# Power.net
KiCad netlist of a schematic drawn in Altium Designer
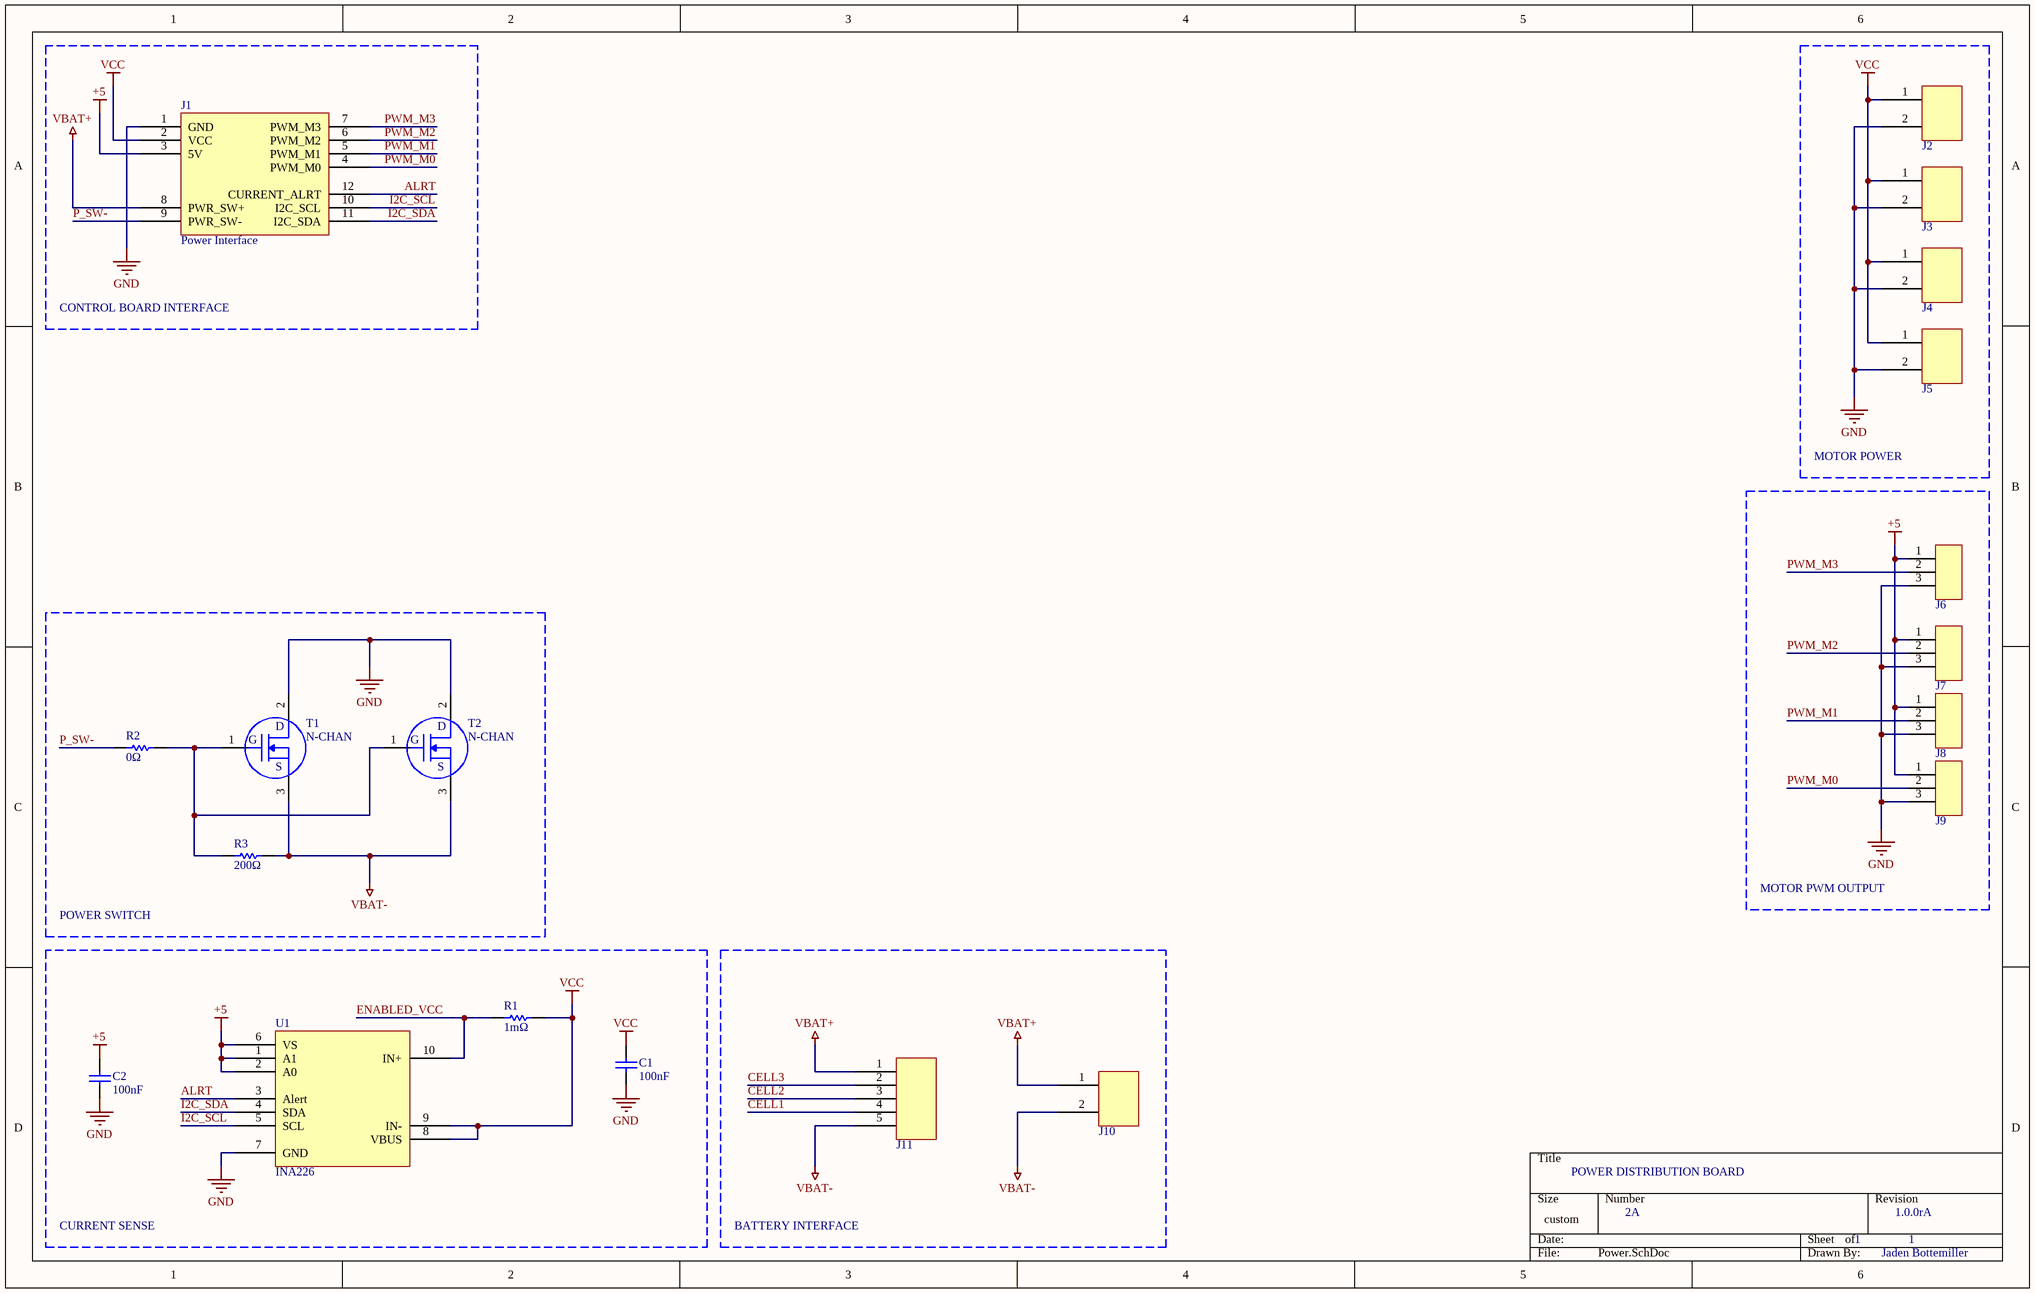
[diagram p0: Power.SchDoc]

(export (version "E")
  (design (tool "Eeschema 10.0.6"))
  (components
    (comp (ref "C1")
      (value "100nF")
      (description "Standard Capacitor")
      (fields (field (name "Comment") "CAP"))
      (libsource (lib "NikoboticsLib") (part "CAP"))
    )
    (comp (ref "C2")
      (value "100nF")
      (description "Standard Capacitor")
      (fields (field (name "Comment") "CAP"))
      (libsource (lib "NikoboticsLib") (part "CAP"))
    )
    (comp (ref "J1")
      (value "Power Interface")
      (description "Interface between power board and control board.")
      (libsource (lib "NikoboticsLib") (part "PDB_INTERFACE"))
    )
    (comp (ref "J2")
      (value "Power Connector")
      (description "Standard Power Connector")
      (libsource (lib "NikoboticsLib") (part "POWER_CONN"))
    )
    (comp (ref "J3")
      (value "Power Connector")
      (description "Standard Power Connector")
      (libsource (lib "NikoboticsLib") (part "POWER_CONN"))
    )
    (comp (ref "J4")
      (value "Power Connector")
      (description "Standard Power Connector")
      (libsource (lib "NikoboticsLib") (part "POWER_CONN"))
    )
    (comp (ref "J5")
      (value "Power Connector")
      (description "Standard Power Connector")
      (libsource (lib "NikoboticsLib") (part "POWER_CONN"))
    )
    (comp (ref "J6")
      (value "3-Pin Signal")
      (description "Standard 3-Pin Signal Connection")
      (libsource (lib "NikoboticsLib") (part "SIG_3PIN"))
    )
    (comp (ref "J7")
      (value "3-Pin Signal")
      (description "Standard 3-Pin Signal Connection")
      (libsource (lib "NikoboticsLib") (part "SIG_3PIN"))
    )
    (comp (ref "J8")
      (value "3-Pin Signal")
      (description "Standard 3-Pin Signal Connection")
      (libsource (lib "NikoboticsLib") (part "SIG_3PIN"))
    )
    (comp (ref "J9")
      (value "3-Pin Signal")
      (description "Standard 3-Pin Signal Connection")
      (libsource (lib "NikoboticsLib") (part "SIG_3PIN"))
    )
    (comp (ref "J10")
      (value "Power Connector")
      (description "Standard Power Connector")
      (libsource (lib "NikoboticsLib") (part "POWER_CONN"))
    )
    (comp (ref "J11")
      (value "5 Pin Connector")
      (description "Standard 5 Pin Connector")
      (libsource (lib "NikoboticsLib") (part "CONN_5PIN"))
    )
    (comp (ref "R1")
      (value "1mΩ")
      (description "Standard Resistor")
      (fields (field (name "Comment") "RES"))
      (libsource (lib "NikoboticsLib") (part "RES"))
    )
    (comp (ref "R2")
      (value "0Ω")
      (description "Standard Resistor")
      (fields (field (name "Comment") "RES"))
      (libsource (lib "NikoboticsLib") (part "RES"))
    )
    (comp (ref "R3")
      (value "200Ω")
      (description "Standard Resistor")
      (fields (field (name "Comment") "RES"))
      (libsource (lib "NikoboticsLib") (part "RES"))
    )
    (comp (ref "T1")
      (value "N-CHAN")
      (description "Standard N-Channel MOSFET. Check pins before designing footprint.")
      (libsource (lib "NikoboticsLib") (part "N-MOSFET"))
    )
    (comp (ref "T2")
      (value "N-CHAN")
      (description "Standard N-Channel MOSFET. Check pins before designing footprint.")
      (libsource (lib "NikoboticsLib") (part "N-MOSFET"))
    )
    (comp (ref "U1")
      (value "INA226")
      (description "Current Monitor Regulator High/Low-Side 10mA")
      (libsource (lib "NikoboticsLib") (part "INA226"))
    )
  )
  (nets
    (net (code "1") (name "+5") (class "Default")
      (node (ref "C2") (pin "2") (pinfunction "2_2") (pintype "passive"))
      (node (ref "J1") (pin "3") (pinfunction "5V_3") (pintype "passive"))
      (node (ref "J6") (pin "1") (pinfunction "Pin_1") (pintype "passive"))
      (node (ref "J7") (pin "1") (pinfunction "Pin_1") (pintype "passive"))
      (node (ref "J8") (pin "1") (pinfunction "Pin_1") (pintype "passive"))
      (node (ref "J9") (pin "1") (pinfunction "Pin_1") (pintype "passive"))
      (node (ref "U1") (pin "1") (pinfunction "A1_1") (pintype "passive"))
      (node (ref "U1") (pin "2") (pinfunction "A0_2") (pintype "passive"))
      (node (ref "U1") (pin "6") (pinfunction "VS_6") (pintype "passive"))
    )
    (net (code "2") (name "/ALRT") (class "Default")
      (node (ref "J1") (pin "12") (pinfunction "CURRENT_ALRT_12") (pintype "passive"))
      (node (ref "U1") (pin "3") (pinfunction "Alert_3") (pintype "passive"))
    )
    (net (code "3") (name "/CELL1") (class "Default")
      (node (ref "J11") (pin "4") (pinfunction "Pin_4") (pintype "passive"))
    )
    (net (code "4") (name "/CELL2") (class "Default")
      (node (ref "J11") (pin "3") (pinfunction "Pin_3") (pintype "passive"))
    )
    (net (code "5") (name "/CELL3") (class "Default")
      (node (ref "J11") (pin "2") (pinfunction "Pin_2") (pintype "passive"))
    )
    (net (code "6") (name "/ENABLED_VCC") (class "Default")
      (node (ref "R1") (pin "1") (pinfunction "1_1") (pintype "passive"))
      (node (ref "U1") (pin "10") (pinfunction "IN+_10") (pintype "passive"))
    )
    (net (code "7") (name "/I2C_SCL") (class "Default")
      (node (ref "J1") (pin "10") (pinfunction "I2C_SCL_10") (pintype "passive"))
      (node (ref "U1") (pin "5") (pinfunction "SCL_5") (pintype "passive"))
    )
    (net (code "8") (name "/I2C_SDA") (class "Default")
      (node (ref "J1") (pin "11") (pinfunction "I2C_SDA_11") (pintype "passive"))
      (node (ref "U1") (pin "4") (pinfunction "SDA_4") (pintype "passive"))
    )
    (net (code "9") (name "/PWM_M0") (class "Default")
      (node (ref "J1") (pin "4") (pinfunction "PWM_M0_4") (pintype "passive"))
      (node (ref "J9") (pin "2") (pinfunction "Pin_2") (pintype "passive"))
    )
    (net (code "10") (name "/PWM_M1") (class "Default")
      (node (ref "J1") (pin "5") (pinfunction "PWM_M1_5") (pintype "passive"))
      (node (ref "J8") (pin "2") (pinfunction "Pin_2") (pintype "passive"))
    )
    (net (code "11") (name "/PWM_M2") (class "Default")
      (node (ref "J1") (pin "6") (pinfunction "PWM_M2_6") (pintype "passive"))
      (node (ref "J7") (pin "2") (pinfunction "Pin_2") (pintype "passive"))
    )
    (net (code "12") (name "/PWM_M3") (class "Default")
      (node (ref "J1") (pin "7") (pinfunction "PWM_M3_7") (pintype "passive"))
      (node (ref "J6") (pin "2") (pinfunction "Pin_2") (pintype "passive"))
    )
    (net (code "13") (name "/P_SW-") (class "Default")
      (node (ref "J1") (pin "9") (pinfunction "PWR_SW-_9") (pintype "passive"))
      (node (ref "R2") (pin "1") (pinfunction "1_1") (pintype "passive"))
    )
    (net (code "14") (name "GND") (class "Default")
      (node (ref "C1") (pin "1") (pinfunction "1_1") (pintype "passive"))
      (node (ref "C2") (pin "1") (pinfunction "1_1") (pintype "passive"))
      (node (ref "J1") (pin "1") (pinfunction "GND_1") (pintype "passive"))
      (node (ref "J2") (pin "2") (pinfunction "Pin_2") (pintype "passive"))
      (node (ref "J3") (pin "2") (pinfunction "Pin_2") (pintype "passive"))
      (node (ref "J4") (pin "2") (pinfunction "Pin_2") (pintype "passive"))
      (node (ref "J5") (pin "2") (pinfunction "Pin_2") (pintype "passive"))
      (node (ref "J6") (pin "3") (pinfunction "Pin_3") (pintype "passive"))
      (node (ref "J7") (pin "3") (pinfunction "Pin_3") (pintype "passive"))
      (node (ref "J8") (pin "3") (pinfunction "Pin_3") (pintype "passive"))
      (node (ref "J9") (pin "3") (pinfunction "Pin_3") (pintype "passive"))
      (node (ref "T1") (pin "2") (pinfunction "Pin_2") (pintype "passive"))
      (node (ref "T2") (pin "2") (pinfunction "Pin_2") (pintype "passive"))
      (node (ref "U1") (pin "7") (pinfunction "GND_7") (pintype "passive"))
    )
    (net (code "15") (name "Net-(R2-Pad2)") (class "Default")
      (node (ref "R2") (pin "2") (pinfunction "2_2") (pintype "passive"))
      (node (ref "R3") (pin "1") (pinfunction "1_1") (pintype "passive"))
      (node (ref "T1") (pin "1") (pinfunction "Pin_1") (pintype "passive"))
      (node (ref "T2") (pin "1") (pinfunction "Pin_1") (pintype "passive"))
    )
    (net (code "16") (name "VBAT+") (class "Default")
      (node (ref "J1") (pin "8") (pinfunction "PWR_SW+_8") (pintype "passive"))
      (node (ref "J10") (pin "1") (pinfunction "Pin_1") (pintype "passive"))
      (node (ref "J11") (pin "1") (pinfunction "Pin_1") (pintype "passive"))
    )
    (net (code "17") (name "VBAT-") (class "Default")
      (node (ref "J10") (pin "2") (pinfunction "Pin_2") (pintype "passive"))
      (node (ref "J11") (pin "5") (pinfunction "Pin_5") (pintype "passive"))
      (node (ref "R3") (pin "2") (pinfunction "2_2") (pintype "passive"))
      (node (ref "T1") (pin "3") (pinfunction "Pin_3") (pintype "passive"))
      (node (ref "T2") (pin "3") (pinfunction "Pin_3") (pintype "passive"))
    )
    (net (code "18") (name "VCC") (class "Default")
      (node (ref "C1") (pin "2") (pinfunction "2_2") (pintype "passive"))
      (node (ref "J1") (pin "2") (pinfunction "VCC_2") (pintype "passive"))
      (node (ref "J2") (pin "1") (pinfunction "Pin_1") (pintype "passive"))
      (node (ref "J3") (pin "1") (pinfunction "Pin_1") (pintype "passive"))
      (node (ref "J4") (pin "1") (pinfunction "Pin_1") (pintype "passive"))
      (node (ref "J5") (pin "1") (pinfunction "Pin_1") (pintype "passive"))
      (node (ref "R1") (pin "2") (pinfunction "2_2") (pintype "passive"))
      (node (ref "U1") (pin "8") (pinfunction "VBUS_8") (pintype "passive"))
      (node (ref "U1") (pin "9") (pinfunction "IN-_9") (pintype "passive"))
    )
  )
)
